# dual_vca_pnl.net
KiCad netlist of a schematic drawn in EAGLE
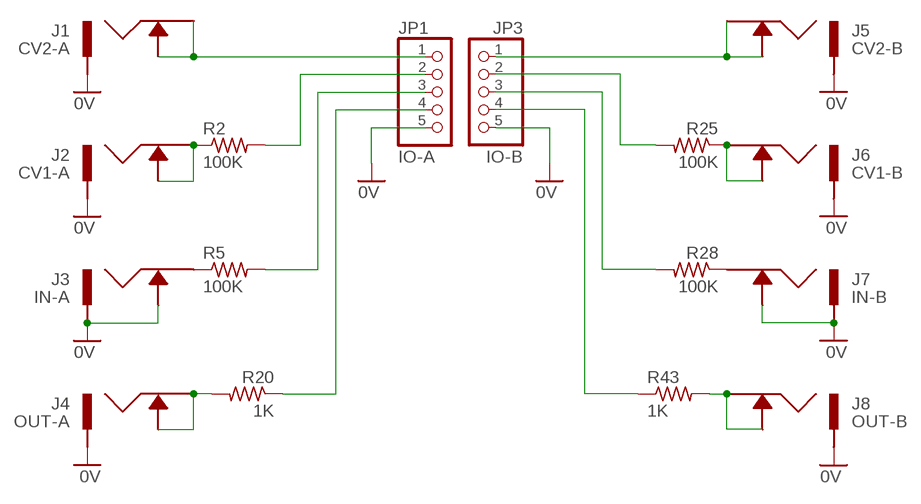
[diagram p0: schematic, sheet 1]

(export (version "E")
  (design (tool "Eeschema 10.0.6"))
  (components
    (comp (ref "J1")
      (value "CV2-A")
      (footprint "eagle-import:ACJM-MV35-2S")
      (libsource (lib "eagle-import") (part "ACJM-MV35-2S"))
    )
    (comp (ref "J2")
      (value "CV1-A")
      (footprint "eagle-import:ACJM-MV35-2S")
      (libsource (lib "eagle-import") (part "ACJM-MV35-2S"))
    )
    (comp (ref "J3")
      (value "IN-A")
      (footprint "eagle-import:ACJM-MV35-2S")
      (libsource (lib "eagle-import") (part "ACJM-MV35-2S"))
    )
    (comp (ref "J4")
      (value "OUT-A")
      (footprint "eagle-import:ACJM-MV35-2S")
      (libsource (lib "eagle-import") (part "ACJM-MV35-2S"))
    )
    (comp (ref "J5")
      (value "CV2-B")
      (footprint "eagle-import:ACJM-MV35-2S")
      (libsource (lib "eagle-import") (part "ACJM-MV35-2S"))
    )
    (comp (ref "J6")
      (value "CV1-B")
      (footprint "eagle-import:ACJM-MV35-2S")
      (libsource (lib "eagle-import") (part "ACJM-MV35-2S"))
    )
    (comp (ref "J7")
      (value "IN-B")
      (footprint "eagle-import:ACJM-MV35-2S")
      (libsource (lib "eagle-import") (part "ACJM-MV35-2S"))
    )
    (comp (ref "J8")
      (value "OUT-B")
      (footprint "eagle-import:ACJM-MV35-2S")
      (libsource (lib "eagle-import") (part "ACJM-MV35-2S"))
    )
    (comp (ref "JP1")
      (value "IO-A")
      (footprint "eagle-import:1X05")
      (libsource (lib "eagle-import") (part "PINHD-1X5"))
    )
    (comp (ref "JP3")
      (value "IO-B")
      (footprint "eagle-import:1X05")
      (libsource (lib "eagle-import") (part "PINHD-1X5"))
    )
    (comp (ref "R2")
      (value "100K")
      (footprint "eagle-import:0207_7")
      (libsource (lib "eagle-import") (part "R-US_0207/7"))
    )
    (comp (ref "R5")
      (value "100K")
      (footprint "eagle-import:0207_7")
      (libsource (lib "eagle-import") (part "R-US_0207/7"))
    )
    (comp (ref "R20")
      (value "1K")
      (footprint "eagle-import:0207_7")
      (libsource (lib "eagle-import") (part "R-US_0207/7"))
    )
    (comp (ref "R25")
      (value "100K")
      (footprint "eagle-import:0207_7")
      (libsource (lib "eagle-import") (part "R-US_0207/7"))
    )
    (comp (ref "R28")
      (value "100K")
      (footprint "eagle-import:0207_7")
      (libsource (lib "eagle-import") (part "R-US_0207/7"))
    )
    (comp (ref "R43")
      (value "1K")
      (footprint "eagle-import:0207_7")
      (libsource (lib "eagle-import") (part "R-US_0207/7"))
    )
  )
  (nets
    (net (code "1") (name "0V") (class "Default")
      (node (ref "J1") (pin "P$1") (pinfunction "P$1_P$1") (pintype "bidirectional"))
      (node (ref "J2") (pin "P$1") (pinfunction "P$1_P$1") (pintype "bidirectional"))
      (node (ref "J3") (pin "P$1") (pinfunction "P$1_P$1") (pintype "bidirectional"))
      (node (ref "J3") (pin "P$2") (pinfunction "P$3_P$2") (pintype "bidirectional"))
      (node (ref "J4") (pin "P$1") (pinfunction "P$1_P$1") (pintype "bidirectional"))
      (node (ref "J5") (pin "P$1") (pinfunction "P$1_P$1") (pintype "bidirectional"))
      (node (ref "J6") (pin "P$1") (pinfunction "P$1_P$1") (pintype "bidirectional"))
      (node (ref "J7") (pin "P$1") (pinfunction "P$1_P$1") (pintype "bidirectional"))
      (node (ref "J7") (pin "P$2") (pinfunction "P$3_P$2") (pintype "bidirectional"))
      (node (ref "J8") (pin "P$1") (pinfunction "P$1_P$1") (pintype "bidirectional"))
      (node (ref "JP1") (pin "5") (pinfunction "5_5") (pintype "passive"))
      (node (ref "JP3") (pin "5") (pinfunction "5_5") (pintype "passive"))
    )
    (net (code "2") (name "Net-(J1-P$2)") (class "Default")
      (node (ref "J1") (pin "P$2") (pinfunction "P$3_P$2") (pintype "bidirectional"))
      (node (ref "J1") (pin "P$3") (pinfunction "P$2_P$3") (pintype "bidirectional"))
      (node (ref "JP1") (pin "1") (pinfunction "1_1") (pintype "passive"))
    )
    (net (code "3") (name "Net-(J2-P$2)") (class "Default")
      (node (ref "J2") (pin "P$2") (pinfunction "P$3_P$2") (pintype "bidirectional"))
      (node (ref "J2") (pin "P$3") (pinfunction "P$2_P$3") (pintype "bidirectional"))
      (node (ref "R2") (pin "1") (pinfunction "1_1") (pintype "passive"))
    )
    (net (code "4") (name "Net-(J3-P$2)") (class "Default")
      (node (ref "J3") (pin "P$3") (pinfunction "P$2_P$3") (pintype "bidirectional"))
      (node (ref "R5") (pin "1") (pinfunction "1_1") (pintype "passive"))
    )
    (net (code "5") (name "Net-(J4-P$2)") (class "Default")
      (node (ref "J4") (pin "P$2") (pinfunction "P$3_P$2") (pintype "bidirectional"))
      (node (ref "J4") (pin "P$3") (pinfunction "P$2_P$3") (pintype "bidirectional"))
      (node (ref "R20") (pin "2") (pinfunction "2_2") (pintype "passive"))
    )
    (net (code "6") (name "Net-(J5-P$2)") (class "Default")
      (node (ref "J5") (pin "P$2") (pinfunction "P$3_P$2") (pintype "bidirectional"))
      (node (ref "J5") (pin "P$3") (pinfunction "P$2_P$3") (pintype "bidirectional"))
      (node (ref "JP3") (pin "1") (pinfunction "1_1") (pintype "passive"))
    )
    (net (code "7") (name "Net-(J6-P$2)") (class "Default")
      (node (ref "J6") (pin "P$2") (pinfunction "P$3_P$2") (pintype "bidirectional"))
      (node (ref "J6") (pin "P$3") (pinfunction "P$2_P$3") (pintype "bidirectional"))
      (node (ref "R25") (pin "1") (pinfunction "1_1") (pintype "passive"))
    )
    (net (code "8") (name "Net-(J7-P$2)") (class "Default")
      (node (ref "J7") (pin "P$3") (pinfunction "P$2_P$3") (pintype "bidirectional"))
      (node (ref "R28") (pin "1") (pinfunction "1_1") (pintype "passive"))
    )
    (net (code "9") (name "Net-(J8-P$2)") (class "Default")
      (node (ref "J8") (pin "P$2") (pinfunction "P$3_P$2") (pintype "bidirectional"))
      (node (ref "J8") (pin "P$3") (pinfunction "P$2_P$3") (pintype "bidirectional"))
      (node (ref "R43") (pin "2") (pinfunction "2_2") (pintype "passive"))
    )
    (net (code "10") (name "Net-(JP1-Pad2)") (class "Default")
      (node (ref "JP1") (pin "2") (pinfunction "2_2") (pintype "passive"))
      (node (ref "R2") (pin "2") (pinfunction "2_2") (pintype "passive"))
    )
    (net (code "11") (name "Net-(JP1-Pad3)") (class "Default")
      (node (ref "JP1") (pin "3") (pinfunction "3_3") (pintype "passive"))
      (node (ref "R5") (pin "2") (pinfunction "2_2") (pintype "passive"))
    )
    (net (code "12") (name "Net-(JP1-Pad4)") (class "Default")
      (node (ref "JP1") (pin "4") (pinfunction "4_4") (pintype "passive"))
      (node (ref "R20") (pin "1") (pinfunction "1_1") (pintype "passive"))
    )
    (net (code "13") (name "Net-(JP3-Pad2)") (class "Default")
      (node (ref "JP3") (pin "2") (pinfunction "2_2") (pintype "passive"))
      (node (ref "R25") (pin "2") (pinfunction "2_2") (pintype "passive"))
    )
    (net (code "14") (name "Net-(JP3-Pad3)") (class "Default")
      (node (ref "JP3") (pin "3") (pinfunction "3_3") (pintype "passive"))
      (node (ref "R28") (pin "2") (pinfunction "2_2") (pintype "passive"))
    )
    (net (code "15") (name "Net-(JP3-Pad4)") (class "Default")
      (node (ref "JP3") (pin "4") (pinfunction "4_4") (pintype "passive"))
      (node (ref "R43") (pin "1") (pinfunction "1_1") (pintype "passive"))
    )
  )
)
